# NUCLEO-F410RB-Motor.net
KiCad netlist of a schematic drawn in Altium Designer
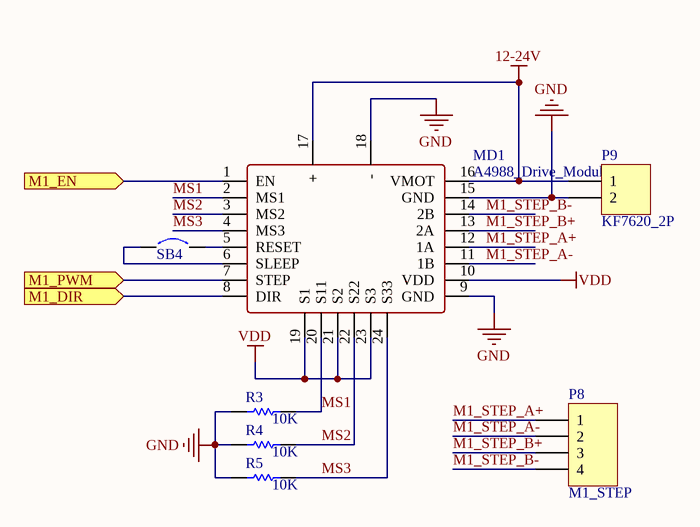
[diagram p0: NUCLEO-F410RB-Motor.SchDoc]

(export (version "E")
  (design (tool "Eeschema 10.0.6"))
  (components
    (comp (ref "MD1")
      (value "A4988_Drive_Module")
      (footprint "A4988_Module")
      (libsource (lib "MotorDriveIC") (part "A4988_Drive_Module"))
    )
    (comp (ref "P8")
      (value "M1_STEP")
      (footprint "HDR1X4-Male")
      (description "Header, 4-Pin")
      (fields (field (name "PUBLISHER") "Altium Limited"))
      (libsource (lib "Connectors") (part "Header 4"))
    )
    (comp (ref "P9")
      (value "KF7620_2P")
      (footprint "KF-7.62-2P")
      (description "KF7620 接线端子")
      (fields (field (name "PUBLISHER") "Altium Limited"))
      (libsource (lib "Connectors") (part "KF7620_2P"))
    )
    (comp (ref "R3")
      (value "10K")
      (footprint "R0603")
      (description "Resistor")
      (fields (field (name "Comment") "Res_US") (field (name "PUBLISHER") "Altium Limited"))
      (libsource (lib "baselib") (part "Res_US"))
    )
    (comp (ref "R4")
      (value "10K")
      (footprint "R0603")
      (description "Resistor")
      (fields (field (name "Comment") "Res_US") (field (name "PUBLISHER") "Altium Limited"))
      (libsource (lib "baselib") (part "Res_US"))
    )
    (comp (ref "R5")
      (value "10K")
      (footprint "R0603")
      (description "Resistor")
      (fields (field (name "Comment") "Res_US") (field (name "PUBLISHER") "Altium Limited"))
      (libsource (lib "baselib") (part "Res_US"))
    )
    (comp (ref "SB4")
      (value "Circuit Breaker")
      (footprint "JP2_SMD")
      (fields (field (name "PUBLISHER") "Altium Limited"))
      (libsource (lib "baselib") (part "Circuit Breaker"))
    )
  )
  (nets
    (net (code "1") (name "/M1_DIR") (class "Default")
      (node (ref "MD1") (pin "8") (pinfunction "DIR_8") (pintype "passive"))
    )
    (net (code "2") (name "/M1_EN") (class "Default")
      (node (ref "MD1") (pin "1") (pinfunction "EN_1") (pintype "passive"))
    )
    (net (code "3") (name "/M1_PWM") (class "Default")
      (node (ref "MD1") (pin "7") (pinfunction "STEP_7") (pintype "passive"))
    )
    (net (code "4") (name "/M1_STEP_A+") (class "Default")
      (node (ref "MD1") (pin "12") (pinfunction "1A_12") (pintype "passive"))
      (node (ref "P8") (pin "1") (pinfunction "1_1") (pintype "passive"))
    )
    (net (code "5") (name "/M1_STEP_A-") (class "Default")
      (node (ref "MD1") (pin "11") (pinfunction "1B_11") (pintype "passive"))
      (node (ref "P8") (pin "2") (pinfunction "2_2") (pintype "passive"))
    )
    (net (code "6") (name "/M1_STEP_B+") (class "Default")
      (node (ref "MD1") (pin "13") (pinfunction "2A_13") (pintype "passive"))
      (node (ref "P8") (pin "3") (pinfunction "3_3") (pintype "passive"))
    )
    (net (code "7") (name "/M1_STEP_B-") (class "Default")
      (node (ref "MD1") (pin "14") (pinfunction "2B_14") (pintype "passive"))
      (node (ref "P8") (pin "4") (pinfunction "4_4") (pintype "passive"))
    )
    (net (code "8") (name "/MS1") (class "Default")
      (node (ref "MD1") (pin "2") (pinfunction "MS1_2") (pintype "passive"))
      (node (ref "MD1") (pin "20") (pinfunction "S11_20") (pintype "passive"))
      (node (ref "R3") (pin "2") (pinfunction "2_2") (pintype "passive"))
    )
    (net (code "9") (name "/MS2") (class "Default")
      (node (ref "MD1") (pin "22") (pinfunction "S22_22") (pintype "passive"))
      (node (ref "MD1") (pin "3") (pinfunction "MS2_3") (pintype "passive"))
      (node (ref "R4") (pin "2") (pinfunction "2_2") (pintype "passive"))
    )
    (net (code "10") (name "/MS3") (class "Default")
      (node (ref "MD1") (pin "24") (pinfunction "S33_24") (pintype "passive"))
      (node (ref "MD1") (pin "4") (pinfunction "MS3_4") (pintype "passive"))
      (node (ref "R5") (pin "2") (pinfunction "2_2") (pintype "passive"))
    )
    (net (code "11") (name "12-24V") (class "Default")
      (node (ref "MD1") (pin "16") (pinfunction "VMOT_16") (pintype "passive"))
      (node (ref "MD1") (pin "17") (pinfunction "+_17") (pintype "passive"))
      (node (ref "P9") (pin "1") (pinfunction "1_1") (pintype "passive"))
    )
    (net (code "12") (name "GND") (class "Default")
      (node (ref "MD1") (pin "15") (pinfunction "GND_15") (pintype "passive"))
      (node (ref "MD1") (pin "18") (pinfunction "-_18") (pintype "passive"))
      (node (ref "MD1") (pin "9") (pinfunction "GND_9") (pintype "passive"))
      (node (ref "P9") (pin "2") (pinfunction "2_2") (pintype "passive"))
      (node (ref "R3") (pin "1") (pinfunction "1_1") (pintype "passive"))
      (node (ref "R4") (pin "1") (pinfunction "1_1") (pintype "passive"))
      (node (ref "R5") (pin "1") (pinfunction "1_1") (pintype "passive"))
    )
    (net (code "13") (name "Net-(MD1-RESET)") (class "Default")
      (node (ref "MD1") (pin "5") (pinfunction "RESET_5") (pintype "passive"))
      (node (ref "SB4") (pin "2") (pinfunction "2_2") (pintype "passive"))
    )
    (net (code "14") (name "Net-(MD1-SLEEP)") (class "Default")
      (node (ref "MD1") (pin "6") (pinfunction "SLEEP_6") (pintype "passive"))
      (node (ref "SB4") (pin "1") (pinfunction "1_1") (pintype "passive"))
    )
    (net (code "15") (name "VDD") (class "Default")
      (node (ref "MD1") (pin "10") (pinfunction "VDD_10") (pintype "passive"))
      (node (ref "MD1") (pin "19") (pinfunction "S1_19") (pintype "passive"))
      (node (ref "MD1") (pin "21") (pinfunction "S2_21") (pintype "passive"))
      (node (ref "MD1") (pin "23") (pinfunction "S3_23") (pintype "passive"))
    )
  )
)
